# CPU.net
KiCad netlist of a schematic drawn in Altium Designer
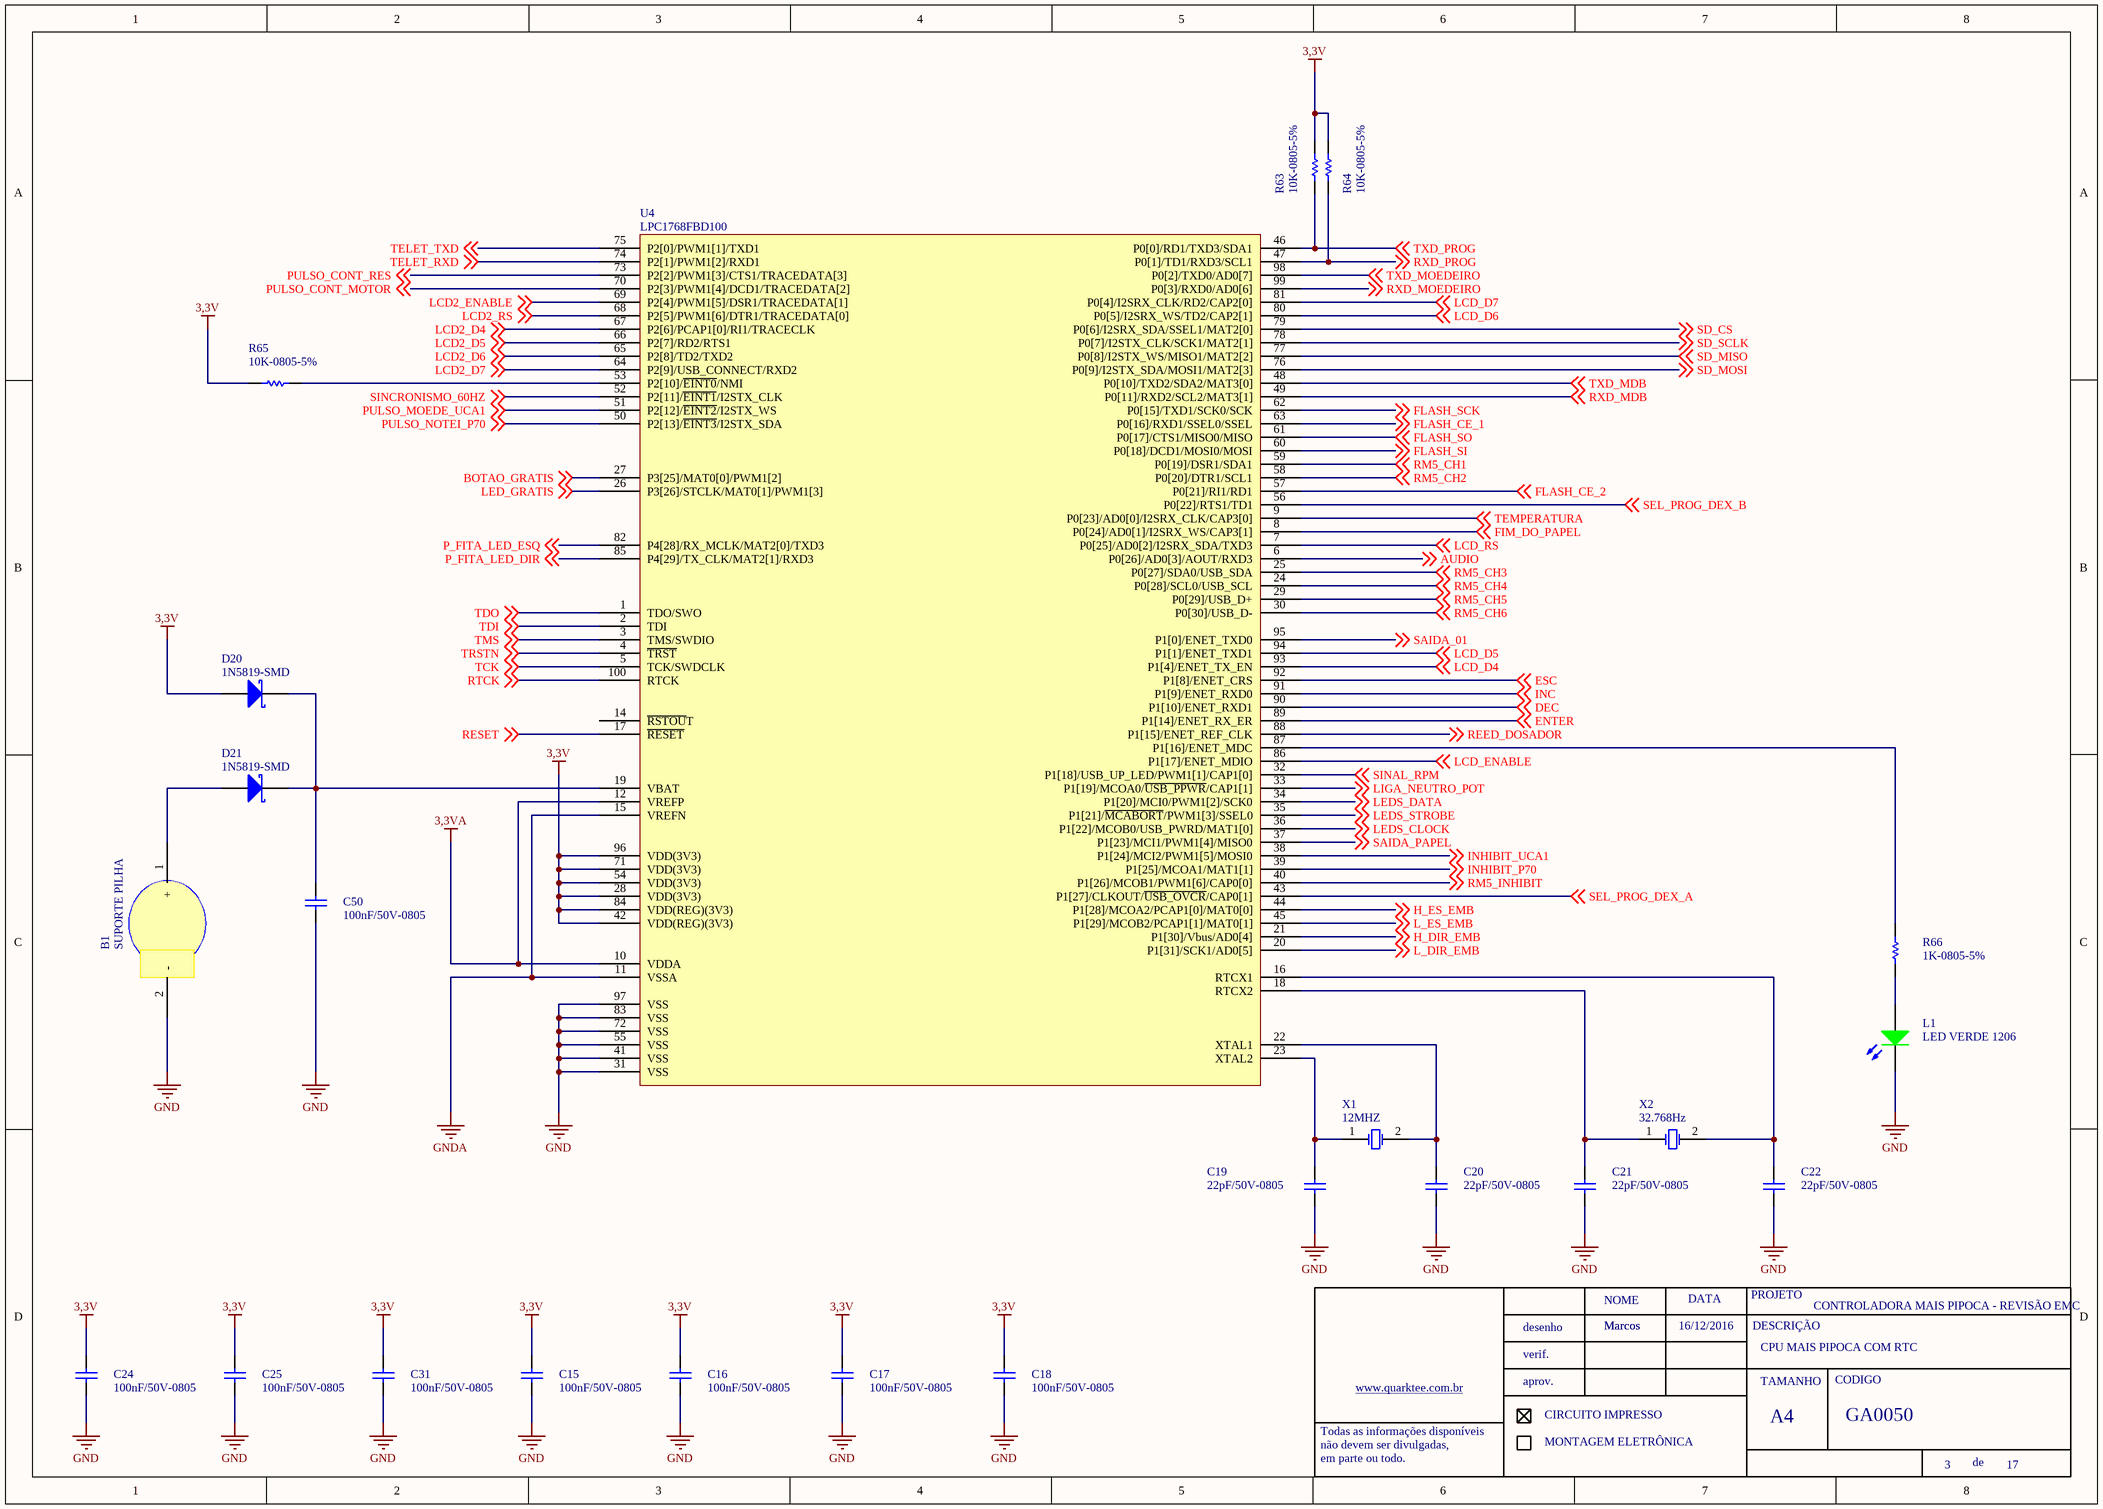
[diagram p0: CPU.SchDoc]

(export (version "E")
  (design (tool "Eeschema 10.0.6"))
  (components
    (comp (ref "B1")
      (value "SUPORTE PILHA")
      (footprint "SUPORTE PILHA CR2032")
      (description "SUPORTE PILHA CR2032")
      (libsource (lib "ChaveDigital3") (part "SUPORTE PILHA CR2032"))
    )
    (comp (ref "C15")
      (value "100nF/50V-0805")
      (footprint "0805-REVISADO ONDA")
      (description "100nF/50-0805-NPO")
      (libsource (lib "AquinoLib") (part "100nF/50-0805-NPO"))
    )
    (comp (ref "C16")
      (value "100nF/50V-0805")
      (footprint "0805-REVISADO ONDA")
      (description "100nF/50-0805-NPO")
      (libsource (lib "AquinoLib") (part "100nF/50-0805-NPO"))
    )
    (comp (ref "C17")
      (value "100nF/50V-0805")
      (footprint "0805-REVISADO ONDA")
      (description "100nF/50-0805-NPO")
      (libsource (lib "AquinoLib") (part "100nF/50-0805-NPO"))
    )
    (comp (ref "C18")
      (value "100nF/50V-0805")
      (footprint "0805-REVISADO ONDA")
      (description "100nF/50-0805-NPO")
      (libsource (lib "AquinoLib") (part "100nF/50-0805-NPO"))
    )
    (comp (ref "C19")
      (value "22pF/50V-0805")
      (footprint "0805-REVISADO ONDA")
      (description "22pF-0805-NPO")
      (libsource (lib "AquinoLib") (part "22pF-0805-NPO"))
    )
    (comp (ref "C20")
      (value "22pF/50V-0805")
      (footprint "0805-REVISADO ONDA")
      (description "22pF-0805-NPO")
      (libsource (lib "AquinoLib") (part "22pF-0805-NPO"))
    )
    (comp (ref "C21")
      (value "22pF/50V-0805")
      (footprint "0805-REVISADO ONDA")
      (description "22pF-0805-NPO")
      (libsource (lib "AquinoLib") (part "22pF-0805-NPO"))
    )
    (comp (ref "C22")
      (value "22pF/50V-0805")
      (footprint "0805-REVISADO ONDA")
      (description "22pF-0805-NPO")
      (libsource (lib "AquinoLib") (part "22pF-0805-NPO"))
    )
    (comp (ref "C24")
      (value "100nF/50V-0805")
      (footprint "0805-REVISADO ONDA")
      (description "100nF/50-0805-NPO")
      (libsource (lib "AquinoLib") (part "100nF/50-0805-NPO"))
    )
    (comp (ref "C25")
      (value "100nF/50V-0805")
      (footprint "0805-REVISADO ONDA")
      (description "100nF/50-0805-NPO")
      (libsource (lib "AquinoLib") (part "100nF/50-0805-NPO"))
    )
    (comp (ref "C31")
      (value "100nF/50V-0805")
      (footprint "0805-REVISADO ONDA")
      (description "100nF/50-0805-NPO")
      (libsource (lib "AquinoLib") (part "100nF/50-0805-NPO"))
    )
    (comp (ref "C50")
      (value "100nF/50V-0805")
      (footprint "0805-REVISADO ONDA")
      (description "100nF/50-0805-NPO")
      (libsource (lib "AquinoLib") (part "100nF/50-0805-NPO"))
    )
    (comp (ref "D20")
      (value "1N5819-SMD")
      (description "1N5819")
      (libsource (lib "ChaveDigital3") (part "1N5819"))
    )
    (comp (ref "D21")
      (value "1N5819-SMD")
      (description "1N5819")
      (libsource (lib "ChaveDigital3") (part "1N5819"))
    )
    (comp (ref "L1")
      (value "LED VERDE 1206")
      (footprint "LED 1206")
      (description "LED VERDE 0603 VERDE")
      (libsource (lib "AquinoLib") (part "LED VERDE 0603 SMD"))
    )
    (comp (ref "R63")
      (value "10K-0805-5%")
      (footprint "0805-REVISADO ONDA")
      (libsource (lib "AquinoLib") (part "10K-0805-5%"))
    )
    (comp (ref "R64")
      (value "10K-0805-5%")
      (footprint "0805-REVISADO ONDA")
      (libsource (lib "AquinoLib") (part "10K-0805-5%"))
    )
    (comp (ref "R65")
      (value "10K-0805-5%")
      (footprint "0805-REVISADO ONDA")
      (libsource (lib "AquinoLib") (part "10K-0805-5%"))
    )
    (comp (ref "R66")
      (value "1K-0805-5%")
      (footprint "0805-REVISADO ONDA")
      (libsource (lib "AquinoLib") (part "1K-0805-5%"))
    )
    (comp (ref "U4")
      (value "LPC1768FBD100")
      (footprint "LQFP-100 pasta")
      (libsource (lib "ChaveDigital3") (part "LPC1768FDB100"))
    )
    (comp (ref "X1")
      (value "12MHZ")
      (footprint "HC49USM")
      (libsource (lib "AquinoLib") (part "CRISTAL 12MHZ"))
    )
    (comp (ref "X2")
      (value "32.768Hz")
      (footprint "CRISTAL TH3")
      (description "CRISTAL 32.768Hz")
      (libsource (lib "AquinoLib") (part "CRISTAL 32.768 Hz"))
    )
  )
  (nets
    (net (code "1") (name "3,3V") (class "Default")
      (node (ref "C15") (pin "2") (pinfunction "2_2") (pintype "passive"))
      (node (ref "C16") (pin "2") (pinfunction "2_2") (pintype "passive"))
      (node (ref "C17") (pin "2") (pinfunction "2_2") (pintype "passive"))
      (node (ref "C18") (pin "2") (pinfunction "2_2") (pintype "passive"))
      (node (ref "C24") (pin "2") (pinfunction "2_2") (pintype "passive"))
      (node (ref "C25") (pin "2") (pinfunction "2_2") (pintype "passive"))
      (node (ref "C31") (pin "2") (pinfunction "2_2") (pintype "passive"))
      (node (ref "D20") (pin "1") (pinfunction "A_1") (pintype "passive"))
      (node (ref "R63") (pin "2") (pinfunction "2_2") (pintype "passive"))
      (node (ref "R64") (pin "2") (pinfunction "2_2") (pintype "passive"))
      (node (ref "R65") (pin "1") (pinfunction "1_1") (pintype "passive"))
      (node (ref "U4") (pin "28") (pinfunction "VDD(3V3)_28") (pintype "passive"))
      (node (ref "U4") (pin "42") (pinfunction "VDD(REG)(3V3)_42") (pintype "passive"))
      (node (ref "U4") (pin "54") (pinfunction "VDD(3V3)_54") (pintype "passive"))
      (node (ref "U4") (pin "71") (pinfunction "VDD(3V3)_71") (pintype "passive"))
      (node (ref "U4") (pin "84") (pinfunction "VDD(REG)(3V3)_84") (pintype "passive"))
      (node (ref "U4") (pin "96") (pinfunction "VDD(3V3)_96") (pintype "passive"))
    )
    (net (code "2") (name "3,3VA") (class "Default")
      (node (ref "U4") (pin "10") (pinfunction "VDDA_10") (pintype "passive"))
      (node (ref "U4") (pin "12") (pinfunction "VREFP_12") (pintype "passive"))
    )
    (net (code "3") (name "AUDIO") (class "Default")
      (node (ref "U4") (pin "6") (pinfunction "P0[26]/AD0[3]/AOUT/RXD3_6") (pintype "passive"))
    )
    (net (code "4") (name "BOTAO_GRATIS") (class "Default")
      (node (ref "U4") (pin "27") (pinfunction "P3[25]/MAT0[0]/PWM1[2]_27") (pintype "passive"))
    )
    (net (code "5") (name "DEC") (class "Default")
      (node (ref "U4") (pin "90") (pinfunction "P1[10]/ENET_RXD1_90") (pintype "passive"))
    )
    (net (code "6") (name "ENTER") (class "Default")
      (node (ref "U4") (pin "89") (pinfunction "P1[14]/ENET_RX_ER_89") (pintype "passive"))
    )
    (net (code "7") (name "ESC") (class "Default")
      (node (ref "U4") (pin "92") (pinfunction "P1[8]/ENET_CRS_92") (pintype "passive"))
    )
    (net (code "8") (name "FIM_DO_PAPEL") (class "Default")
      (node (ref "U4") (pin "8") (pinfunction "P0[24]/AD0[1]/I2SRX_WS/CAP3[1]_8") (pintype "passive"))
    )
    (net (code "9") (name "FLASH_CE_1") (class "Default")
      (node (ref "U4") (pin "63") (pinfunction "P0[16]/RXD1/SSEL0/SSEL_63") (pintype "passive"))
    )
    (net (code "10") (name "FLASH_CE_2") (class "Default")
      (node (ref "U4") (pin "57") (pinfunction "P0[21]/RI1/RD1_57") (pintype "passive"))
    )
    (net (code "11") (name "FLASH_SCK") (class "Default")
      (node (ref "U4") (pin "62") (pinfunction "P0[15]/TXD1/SCK0/SCK_62") (pintype "passive"))
    )
    (net (code "12") (name "FLASH_SI") (class "Default")
      (node (ref "U4") (pin "60") (pinfunction "P0[18]/DCD1/MOSI0/MOSI_60") (pintype "passive"))
    )
    (net (code "13") (name "FLASH_SO") (class "Default")
      (node (ref "U4") (pin "61") (pinfunction "P0[17]/CTS1/MISO0/MISO_61") (pintype "passive"))
    )
    (net (code "14") (name "GND") (class "Default")
      (node (ref "B1") (pin "2") (pinfunction "-_2") (pintype "passive"))
      (node (ref "C15") (pin "1") (pinfunction "1_1") (pintype "passive"))
      (node (ref "C16") (pin "1") (pinfunction "1_1") (pintype "passive"))
      (node (ref "C17") (pin "1") (pinfunction "1_1") (pintype "passive"))
      (node (ref "C18") (pin "1") (pinfunction "1_1") (pintype "passive"))
      (node (ref "C19") (pin "1") (pinfunction "1_1") (pintype "passive"))
      (node (ref "C20") (pin "1") (pinfunction "1_1") (pintype "passive"))
      (node (ref "C21") (pin "1") (pinfunction "1_1") (pintype "passive"))
      (node (ref "C22") (pin "1") (pinfunction "1_1") (pintype "passive"))
      (node (ref "C24") (pin "1") (pinfunction "1_1") (pintype "passive"))
      (node (ref "C25") (pin "1") (pinfunction "1_1") (pintype "passive"))
      (node (ref "C31") (pin "1") (pinfunction "1_1") (pintype "passive"))
      (node (ref "C50") (pin "1") (pinfunction "1_1") (pintype "passive"))
      (node (ref "L1") (pin "2") (pinfunction "K_2") (pintype "passive"))
      (node (ref "U4") (pin "31") (pinfunction "VSS_31") (pintype "passive"))
      (node (ref "U4") (pin "41") (pinfunction "VSS_41") (pintype "passive"))
      (node (ref "U4") (pin "55") (pinfunction "VSS_55") (pintype "passive"))
      (node (ref "U4") (pin "72") (pinfunction "VSS_72") (pintype "passive"))
      (node (ref "U4") (pin "83") (pinfunction "VSS_83") (pintype "passive"))
      (node (ref "U4") (pin "97") (pinfunction "VSS_97") (pintype "passive"))
    )
    (net (code "15") (name "GNDA") (class "Default")
      (node (ref "U4") (pin "11") (pinfunction "VSSA_11") (pintype "passive"))
      (node (ref "U4") (pin "15") (pinfunction "VREFN_15") (pintype "passive"))
    )
    (net (code "16") (name "H_DIR_EMB") (class "Default")
      (node (ref "U4") (pin "21") (pinfunction "P1[30]/Vbus/AD0[4]_21") (pintype "passive"))
    )
    (net (code "17") (name "H_ES_EMB") (class "Default")
      (node (ref "U4") (pin "44") (pinfunction "P1[28]/MCOA2/PCAP1[0]/MAT0[0]_44") (pintype "passive"))
    )
    (net (code "18") (name "INC") (class "Default")
      (node (ref "U4") (pin "91") (pinfunction "P1[9]/ENET_RXD0_91") (pintype "passive"))
    )
    (net (code "19") (name "INHIBIT_P70") (class "Default")
      (node (ref "U4") (pin "39") (pinfunction "P1[25]/MCOA1/MAT1[1]_39") (pintype "passive"))
    )
    (net (code "20") (name "INHIBIT_UCA1") (class "Default")
      (node (ref "U4") (pin "38") (pinfunction "P1[24]/MCI2/PWM1[5]/MOSI0_38") (pintype "passive"))
    )
    (net (code "21") (name "LCD2_D4") (class "Default")
      (node (ref "U4") (pin "67") (pinfunction "P2[6]/PCAP1[0]/RI1/TRACECLK_67") (pintype "passive"))
    )
    (net (code "22") (name "LCD2_D5") (class "Default")
      (node (ref "U4") (pin "66") (pinfunction "P2[7]/RD2/RTS1_66") (pintype "passive"))
    )
    (net (code "23") (name "LCD2_D6") (class "Default")
      (node (ref "U4") (pin "65") (pinfunction "P2[8]/TD2/TXD2_65") (pintype "passive"))
    )
    (net (code "24") (name "LCD2_D7") (class "Default")
      (node (ref "U4") (pin "64") (pinfunction "P2[9]/USB_CONNECT/RXD2_64") (pintype "passive"))
    )
    (net (code "25") (name "LCD2_ENABLE") (class "Default")
      (node (ref "U4") (pin "69") (pinfunction "P2[4]/PWM1[5]/DSR1/TRACEDATA[1]_69") (pintype "passive"))
    )
    (net (code "26") (name "LCD2_RS") (class "Default")
      (node (ref "U4") (pin "68") (pinfunction "P2[5]/PWM1[6]/DTR1/TRACEDATA[0]_68") (pintype "passive"))
    )
    (net (code "27") (name "LCD_D4") (class "Default")
      (node (ref "U4") (pin "93") (pinfunction "P1[4]/ENET_TX_EN_93") (pintype "passive"))
    )
    (net (code "28") (name "LCD_D5") (class "Default")
      (node (ref "U4") (pin "94") (pinfunction "P1[1]/ENET_TXD1_94") (pintype "passive"))
    )
    (net (code "29") (name "LCD_D6") (class "Default")
      (node (ref "U4") (pin "80") (pinfunction "P0[5]/I2SRX_WS/TD2/CAP2[1]_80") (pintype "passive"))
    )
    (net (code "30") (name "LCD_D7") (class "Default")
      (node (ref "U4") (pin "81") (pinfunction "P0[4]/I2SRX_CLK/RD2/CAP2[0]_81") (pintype "passive"))
    )
    (net (code "31") (name "LCD_ENABLE") (class "Default")
      (node (ref "U4") (pin "86") (pinfunction "P1[17]/ENET_MDIO_86") (pintype "passive"))
    )
    (net (code "32") (name "LCD_RS") (class "Default")
      (node (ref "U4") (pin "7") (pinfunction "P0[25]/AD0[2]/I2SRX_SDA/TXD3_7") (pintype "passive"))
    )
    (net (code "33") (name "LEDS_CLOCK") (class "Default")
      (node (ref "U4") (pin "36") (pinfunction "P1[22]/MCOB0/USB_PWRD/MAT1[0]_36") (pintype "passive"))
    )
    (net (code "34") (name "LEDS_DATA") (class "Default")
      (node (ref "U4") (pin "34") (pinfunction "P1[20]/MCI0/PWM1[2]/SCK0_34") (pintype "passive"))
    )
    (net (code "35") (name "LEDS_STROBE") (class "Default")
      (node (ref "U4") (pin "35") (pinfunction "P1[21]/~{MCABORT}/PWM1[3]/SSEL0_35") (pintype "passive"))
    )
    (net (code "36") (name "LED_GRATIS") (class "Default")
      (node (ref "U4") (pin "26") (pinfunction "P3[26]/STCLK/MAT0[1]/PWM1[3]_26") (pintype "passive"))
    )
    (net (code "37") (name "LIGA_NEUTRO_POT") (class "Default")
      (node (ref "U4") (pin "33") (pinfunction "P1[19]/MCOA0/~{USB_PPWR}/CAP1[1]_33") (pintype "passive"))
    )
    (net (code "38") (name "L_DIR_EMB") (class "Default")
      (node (ref "U4") (pin "20") (pinfunction "P1[31]/SCK1/AD0[5]_20") (pintype "passive"))
    )
    (net (code "39") (name "L_ES_EMB") (class "Default")
      (node (ref "U4") (pin "45") (pinfunction "P1[29]/MCOB2/PCAP1[1]/MAT0[1]_45") (pintype "passive"))
    )
    (net (code "40") (name "Net-(B1-+)") (class "Default")
      (node (ref "B1") (pin "1") (pinfunction "+_1") (pintype "passive"))
      (node (ref "D21") (pin "1") (pinfunction "A_1") (pintype "passive"))
    )
    (net (code "41") (name "Net-(D20-K)") (class "Default")
      (node (ref "C50") (pin "2") (pinfunction "2_2") (pintype "passive"))
      (node (ref "D20") (pin "2") (pinfunction "K_2") (pintype "passive"))
      (node (ref "D21") (pin "2") (pinfunction "K_2") (pintype "passive"))
      (node (ref "U4") (pin "19") (pinfunction "VBAT_19") (pintype "passive"))
    )
    (net (code "42") (name "Net-(L1-A)") (class "Default")
      (node (ref "L1") (pin "1") (pinfunction "A_1") (pintype "passive"))
      (node (ref "R66") (pin "1") (pinfunction "1_1") (pintype "passive"))
    )
    (net (code "43") (name "Net-(U4-P1[16]{slash}ENET_MDC)") (class "Default")
      (node (ref "R66") (pin "2") (pinfunction "2_2") (pintype "passive"))
      (node (ref "U4") (pin "87") (pinfunction "P1[16]/ENET_MDC_87") (pintype "passive"))
    )
    (net (code "44") (name "Net-(U4-P2[10]{slash}~{EINT0}{slash}NMI)") (class "Default")
      (node (ref "R65") (pin "2") (pinfunction "2_2") (pintype "passive"))
      (node (ref "U4") (pin "53") (pinfunction "P2[10]/~{EINT0}/NMI_53") (pintype "passive"))
    )
    (net (code "45") (name "Net-(U4-RTCX1)") (class "Default")
      (node (ref "C22") (pin "2") (pinfunction "2_2") (pintype "passive"))
      (node (ref "U4") (pin "16") (pinfunction "RTCX1_16") (pintype "passive"))
      (node (ref "X2") (pin "2") (pinfunction "OSC2_2") (pintype "passive"))
    )
    (net (code "46") (name "Net-(U4-RTCX2)") (class "Default")
      (node (ref "C21") (pin "2") (pinfunction "2_2") (pintype "passive"))
      (node (ref "U4") (pin "18") (pinfunction "RTCX2_18") (pintype "passive"))
      (node (ref "X2") (pin "1") (pinfunction "OSC1_1") (pintype "passive"))
    )
    (net (code "47") (name "Net-(U4-XTAL1)") (class "Default")
      (node (ref "C20") (pin "2") (pinfunction "2_2") (pintype "passive"))
      (node (ref "U4") (pin "22") (pinfunction "XTAL1_22") (pintype "passive"))
      (node (ref "X1") (pin "2") (pinfunction "OSC2_2") (pintype "passive"))
    )
    (net (code "48") (name "Net-(U4-XTAL2)") (class "Default")
      (node (ref "C19") (pin "2") (pinfunction "2_2") (pintype "passive"))
      (node (ref "U4") (pin "23") (pinfunction "XTAL2_23") (pintype "passive"))
      (node (ref "X1") (pin "1") (pinfunction "OSC1_1") (pintype "passive"))
    )
    (net (code "49") (name "PULSO_CONT_MOTOR") (class "Default")
      (node (ref "U4") (pin "70") (pinfunction "P2[3]/PWM1[4]/DCD1/TRACEDATA[2]_70") (pintype "passive"))
    )
    (net (code "50") (name "PULSO_CONT_RES") (class "Default")
      (node (ref "U4") (pin "73") (pinfunction "P2[2]/PWM1[3]/CTS1/TRACEDATA[3]_73") (pintype "passive"))
    )
    (net (code "51") (name "PULSO_MOEDE_UCA1") (class "Default")
      (node (ref "U4") (pin "51") (pinfunction "P2[12]/~{EINT2}/I2STX_WS_51") (pintype "passive"))
    )
    (net (code "52") (name "PULSO_NOTEI_P70") (class "Default")
      (node (ref "U4") (pin "50") (pinfunction "P2[13]/~{EINT3}/I2STX_SDA_50") (pintype "passive"))
    )
    (net (code "53") (name "P_FITA_LED_DIR") (class "Default")
      (node (ref "U4") (pin "85") (pinfunction "P4[29]/TX_CLK/MAT2[1]/RXD3_85") (pintype "passive"))
    )
    (net (code "54") (name "P_FITA_LED_ESQ") (class "Default")
      (node (ref "U4") (pin "82") (pinfunction "P4[28]/RX_MCLK/MAT2[0]/TXD3_82") (pintype "passive"))
    )
    (net (code "55") (name "REED_DOSADOR") (class "Default")
      (node (ref "U4") (pin "88") (pinfunction "P1[15]/ENET_REF_CLK_88") (pintype "passive"))
    )
    (net (code "56") (name "RESET") (class "Default")
      (node (ref "U4") (pin "17") (pinfunction "~{RESET}_17") (pintype "passive"))
    )
    (net (code "57") (name "RM5_CH1") (class "Default")
      (node (ref "U4") (pin "59") (pinfunction "P0[19]/DSR1/SDA1_59") (pintype "passive"))
    )
    (net (code "58") (name "RM5_CH2") (class "Default")
      (node (ref "U4") (pin "58") (pinfunction "P0[20]/DTR1/SCL1_58") (pintype "passive"))
    )
    (net (code "59") (name "RM5_CH3") (class "Default")
      (node (ref "U4") (pin "25") (pinfunction "P0[27]/SDA0/USB_SDA_25") (pintype "passive"))
    )
    (net (code "60") (name "RM5_CH4") (class "Default")
      (node (ref "U4") (pin "24") (pinfunction "P0[28]/SCL0/USB_SCL_24") (pintype "passive"))
    )
    (net (code "61") (name "RM5_CH5") (class "Default")
      (node (ref "U4") (pin "29") (pinfunction "P0[29]/USB_D+_29") (pintype "passive"))
    )
    (net (code "62") (name "RM5_CH6") (class "Default")
      (node (ref "U4") (pin "30") (pinfunction "P0[30]/USB_D-_30") (pintype "passive"))
    )
    (net (code "63") (name "RM5_INHIBIT") (class "Default")
      (node (ref "U4") (pin "40") (pinfunction "P1[26]/MCOB1/PWM1[6]/CAP0[0]_40") (pintype "passive"))
    )
    (net (code "64") (name "RTCK") (class "Default")
      (node (ref "U4") (pin "100") (pinfunction "RTCK_100") (pintype "passive"))
    )
    (net (code "65") (name "RXD_MDB") (class "Default")
      (node (ref "U4") (pin "49") (pinfunction "P0[11]/RXD2/SCL2/MAT3[1]_49") (pintype "passive"))
    )
    (net (code "66") (name "RXD_MOEDEIRO") (class "Default")
      (node (ref "U4") (pin "99") (pinfunction "P0[3]/RXD0/AD0[6]_99") (pintype "passive"))
    )
    (net (code "67") (name "RXD_PROG") (class "Default")
      (node (ref "R64") (pin "1") (pinfunction "1_1") (pintype "passive"))
      (node (ref "U4") (pin "47") (pinfunction "P0[1]/TD1/RXD3/SCL1_47") (pintype "passive"))
    )
    (net (code "68") (name "SAIDA_01") (class "Default")
      (node (ref "U4") (pin "95") (pinfunction "P1[0]/ENET_TXD0_95") (pintype "passive"))
    )
    (net (code "69") (name "SAIDA_PAPEL") (class "Default")
      (node (ref "U4") (pin "37") (pinfunction "P1[23]/MCI1/PWM1[4]/MISO0_37") (pintype "passive"))
    )
    (net (code "70") (name "SD_CS") (class "Default")
      (node (ref "U4") (pin "79") (pinfunction "P0[6]/I2SRX_SDA/SSEL1/MAT2[0]_79") (pintype "passive"))
    )
    (net (code "71") (name "SD_MISO") (class "Default")
      (node (ref "U4") (pin "77") (pinfunction "P0[8]/I2STX_WS/MISO1/MAT2[2]_77") (pintype "passive"))
    )
    (net (code "72") (name "SD_MOSI") (class "Default")
      (node (ref "U4") (pin "76") (pinfunction "P0[9]/I2STX_SDA/MOSI1/MAT2[3]_76") (pintype "passive"))
    )
    (net (code "73") (name "SD_SCLK") (class "Default")
      (node (ref "U4") (pin "78") (pinfunction "P0[7]/I2STX_CLK/SCK1/MAT2[1]_78") (pintype "passive"))
    )
    (net (code "74") (name "SEL_PROG_DEX_A") (class "Default")
      (node (ref "U4") (pin "43") (pinfunction "P1[27]/CLKOUT/~{USB_OVCR}/CAP0[1]_43") (pintype "passive"))
    )
    (net (code "75") (name "SEL_PROG_DEX_B") (class "Default")
      (node (ref "U4") (pin "56") (pinfunction "P0[22]/RTS1/TD1_56") (pintype "passive"))
    )
    (net (code "76") (name "SINAL_RPM") (class "Default")
      (node (ref "U4") (pin "32") (pinfunction "P1[18]/USB_UP_LED/PWM1[1]/CAP1[0]_32") (pintype "passive"))
    )
    (net (code "77") (name "SINCRONISMO_60HZ") (class "Default")
      (node (ref "U4") (pin "52") (pinfunction "P2[11]/~{EINT1}/I2STX_CLK_52") (pintype "passive"))
    )
    (net (code "78") (name "TCK") (class "Default")
      (node (ref "U4") (pin "5") (pinfunction "TCK/SWDCLK_5") (pintype "passive"))
    )
    (net (code "79") (name "TDI") (class "Default")
      (node (ref "U4") (pin "2") (pinfunction "TDI_2") (pintype "passive"))
    )
    (net (code "80") (name "TDO") (class "Default")
      (node (ref "U4") (pin "1") (pinfunction "TDO/SWO_1") (pintype "passive"))
    )
    (net (code "81") (name "TELET_RXD") (class "Default")
      (node (ref "U4") (pin "74") (pinfunction "P2[1]/PWM1[2]/RXD1_74") (pintype "passive"))
    )
    (net (code "82") (name "TELET_TXD") (class "Default")
      (node (ref "U4") (pin "75") (pinfunction "P2[0]/PWM1[1]/TXD1_75") (pintype "passive"))
    )
    (net (code "83") (name "TEMPERATURA") (class "Default")
      (node (ref "U4") (pin "9") (pinfunction "P0[23]/AD0[0]/I2SRX_CLK/CAP3[0]_9") (pintype "passive"))
    )
    (net (code "84") (name "TMS") (class "Default")
      (node (ref "U4") (pin "3") (pinfunction "TMS/SWDIO_3") (pintype "passive"))
    )
    (net (code "85") (name "TRSTN") (class "Default")
      (node (ref "U4") (pin "4") (pinfunction "~{TRST}_4") (pintype "passive"))
    )
    (net (code "86") (name "TXD_MDB") (class "Default")
      (node (ref "U4") (pin "48") (pinfunction "P0[10]/TXD2/SDA2/MAT3[0]_48") (pintype "passive"))
    )
    (net (code "87") (name "TXD_MOEDEIRO") (class "Default")
      (node (ref "U4") (pin "98") (pinfunction "P0[2]/TXD0/AD0[7]_98") (pintype "passive"))
    )
    (net (code "88") (name "TXD_PROG") (class "Default")
      (node (ref "R63") (pin "1") (pinfunction "1_1") (pintype "passive"))
      (node (ref "U4") (pin "46") (pinfunction "P0[0]/RD1/TXD3/SDA1_46") (pintype "passive"))
    )
    (net (code "89") (name "unconnected-(U4-~{RSTOU}T-Pad14)") (class "Default")
      (node (ref "U4") (pin "14") (pinfunction "~{RSTOU}T_14") (pintype "passive"))
    )
  )
)
